# badge.net
KiCad netlist of a schematic drawn in EAGLE
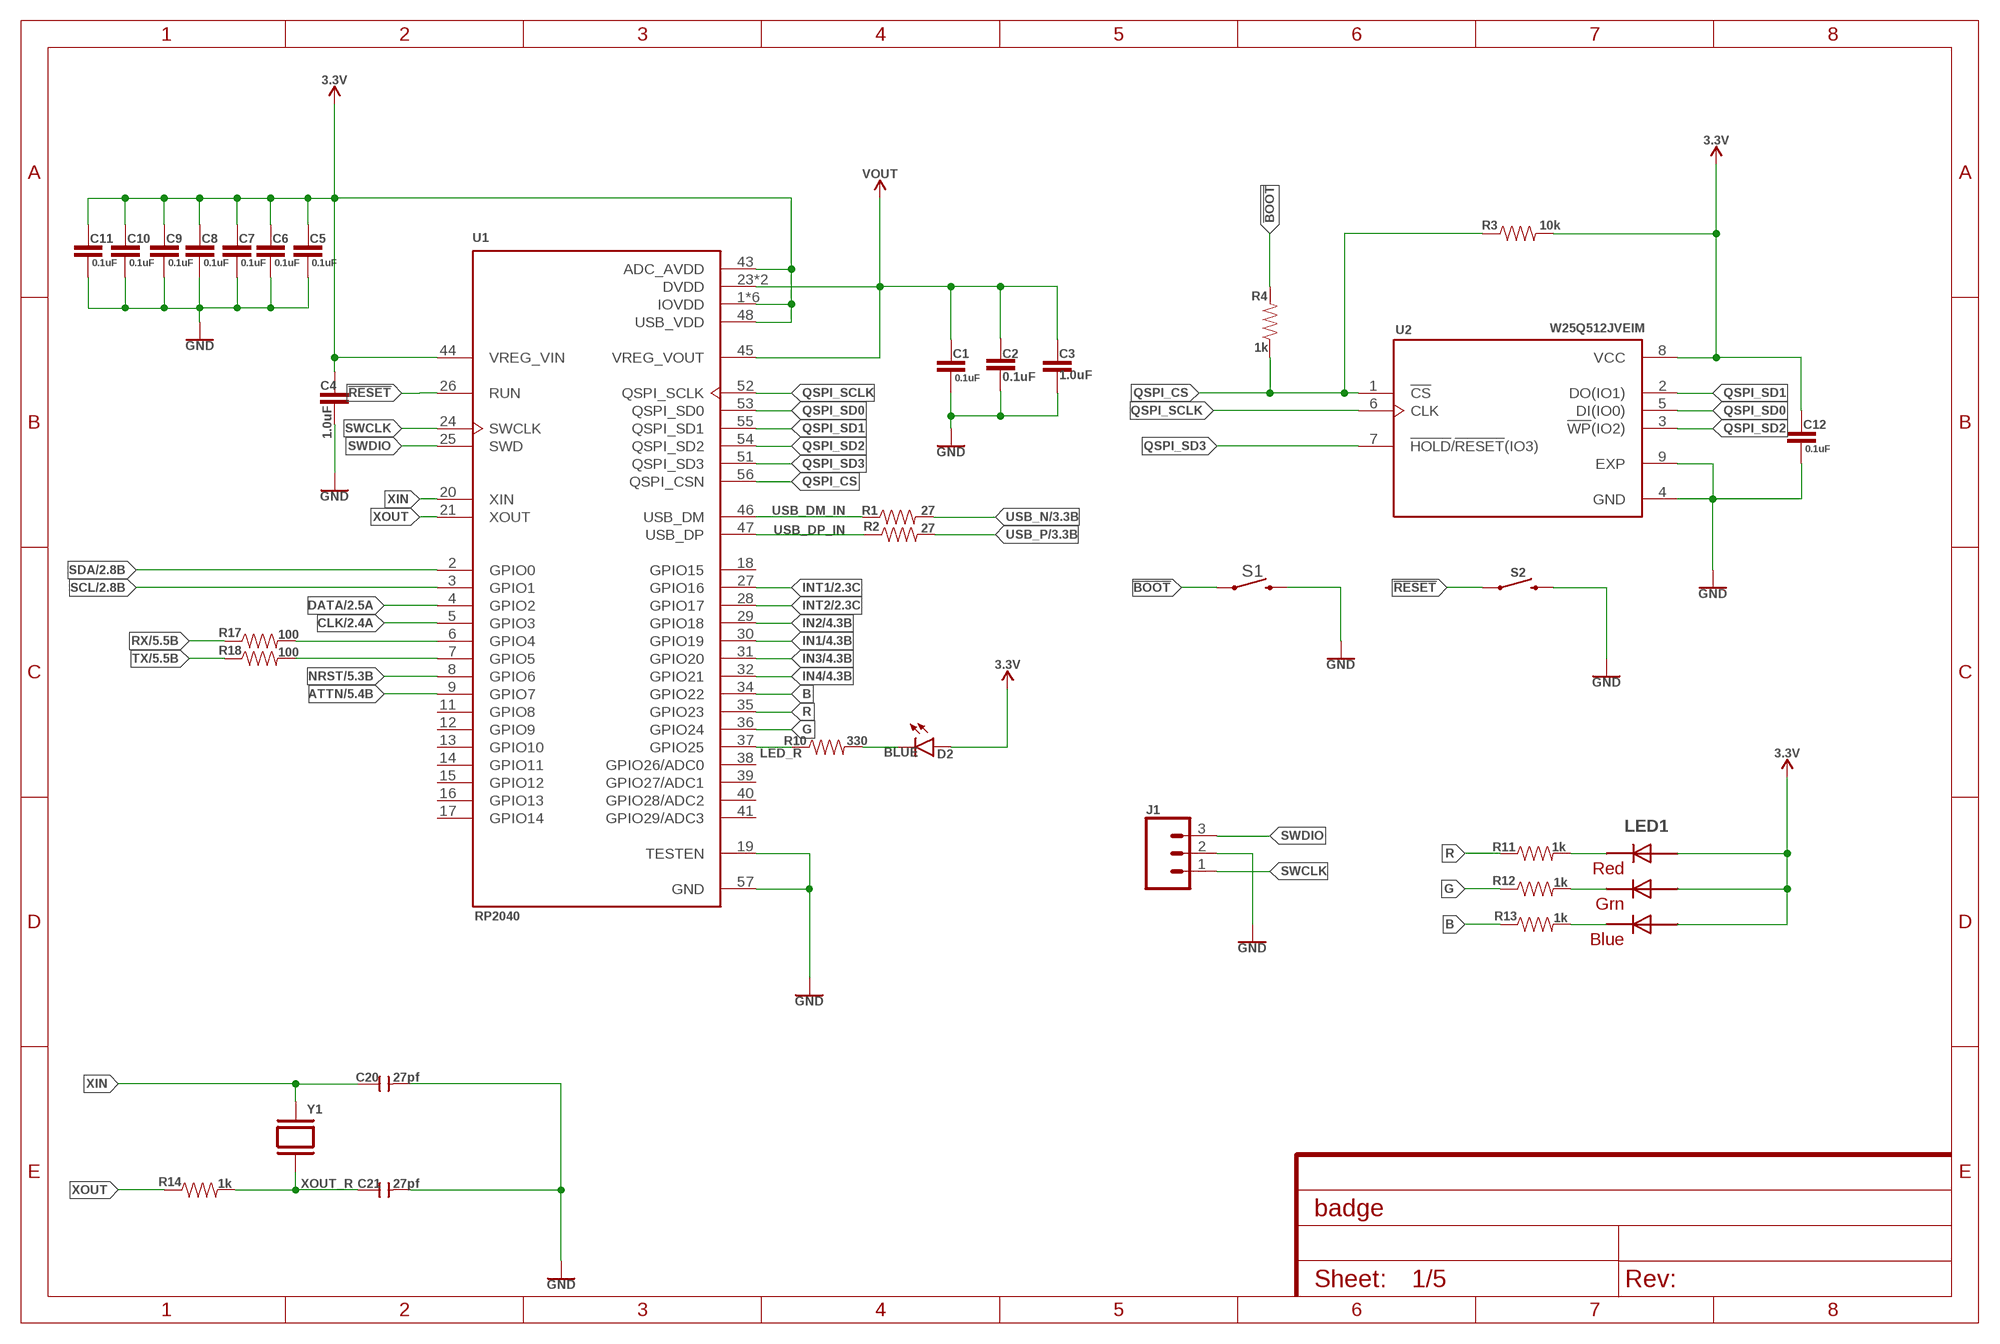
[diagram p0: schematic, sheet 1]
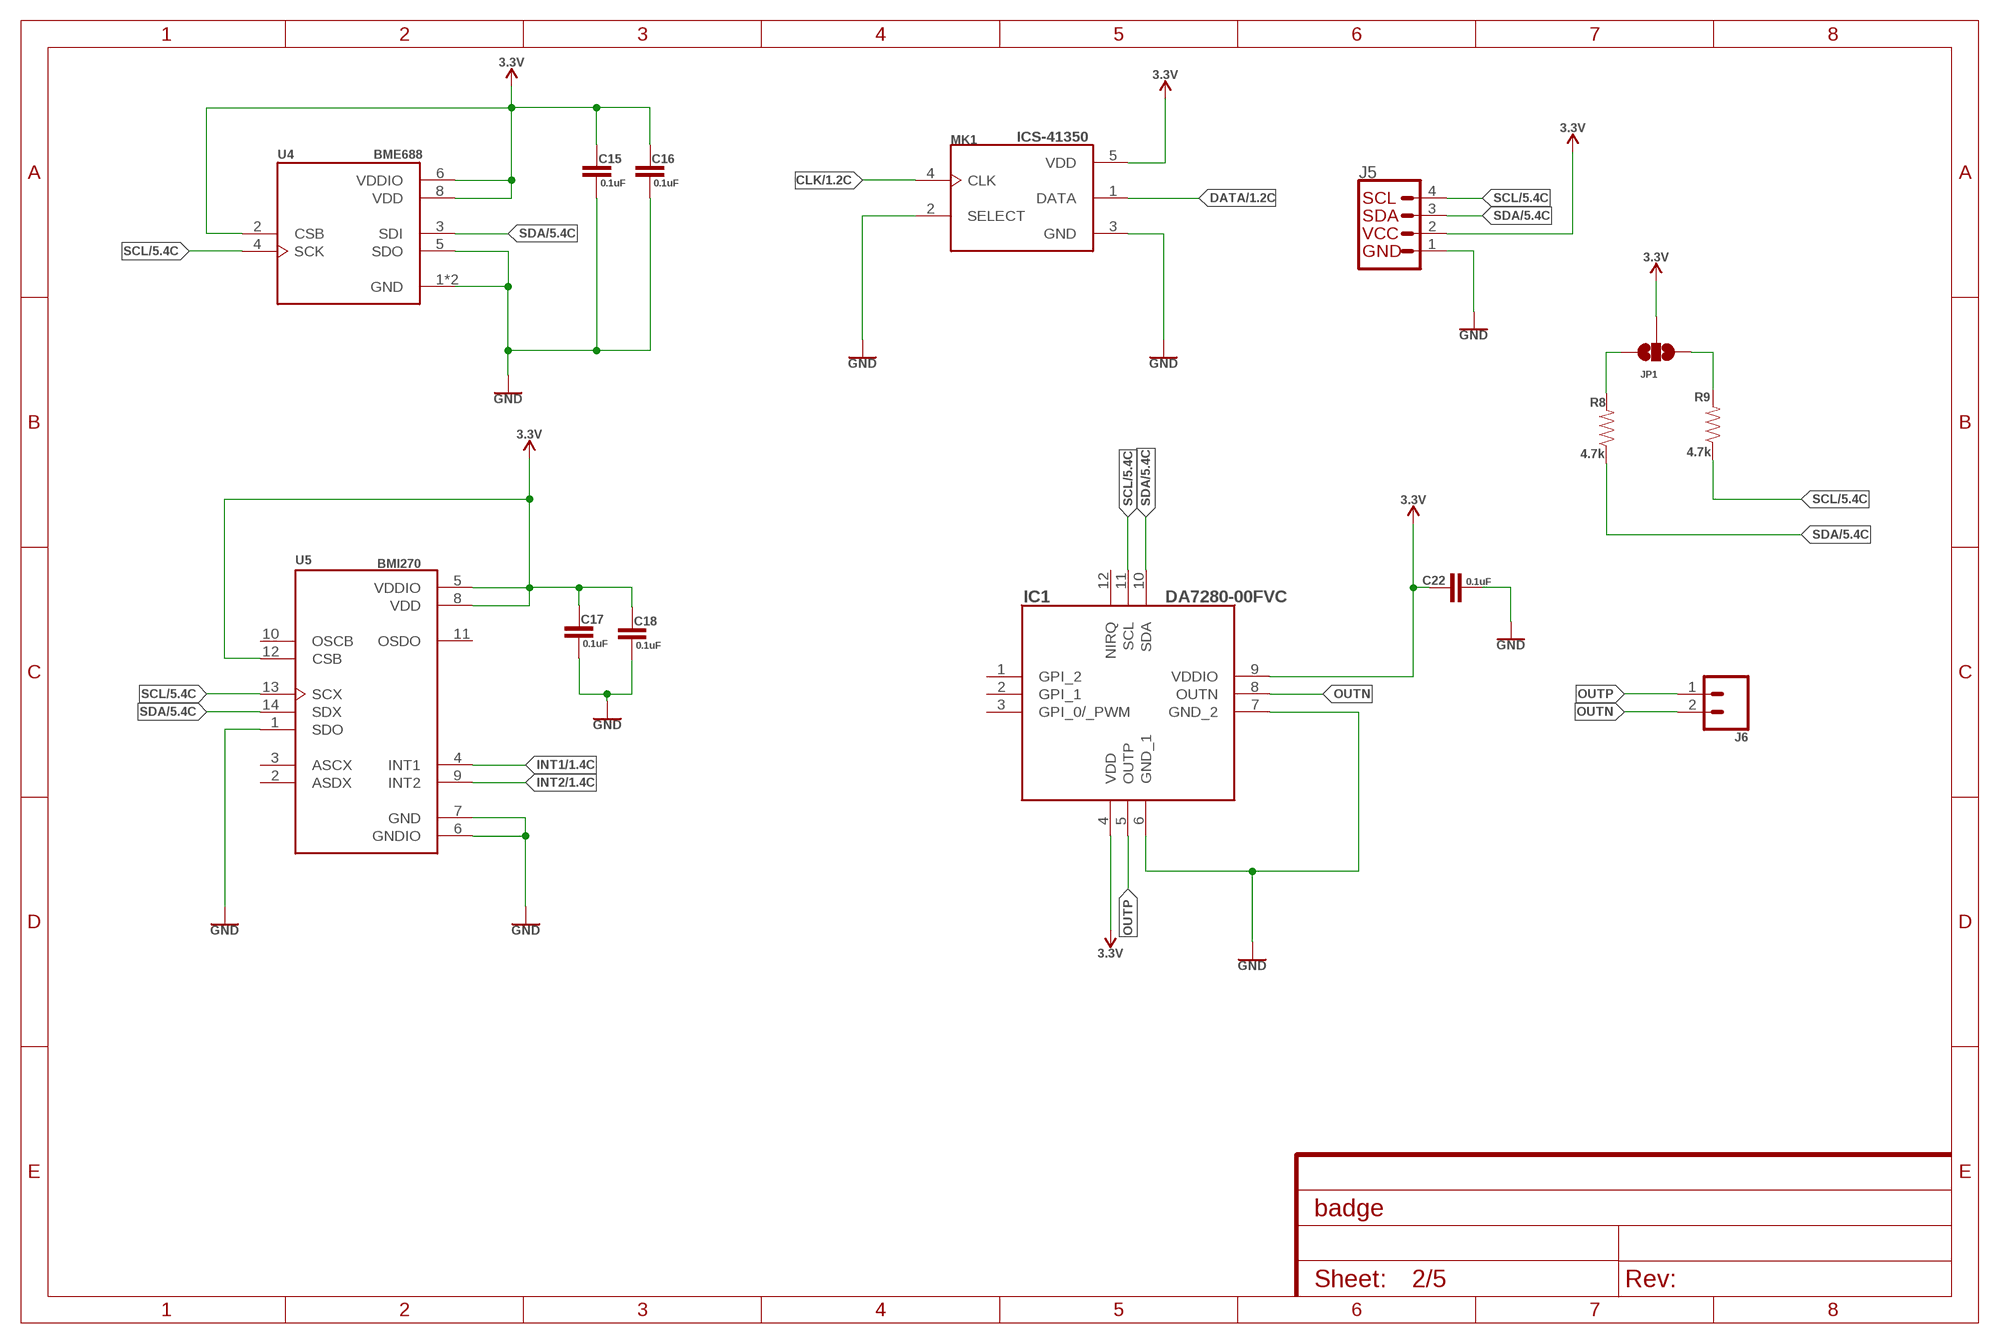
[diagram p1: schematic, sheet 2]
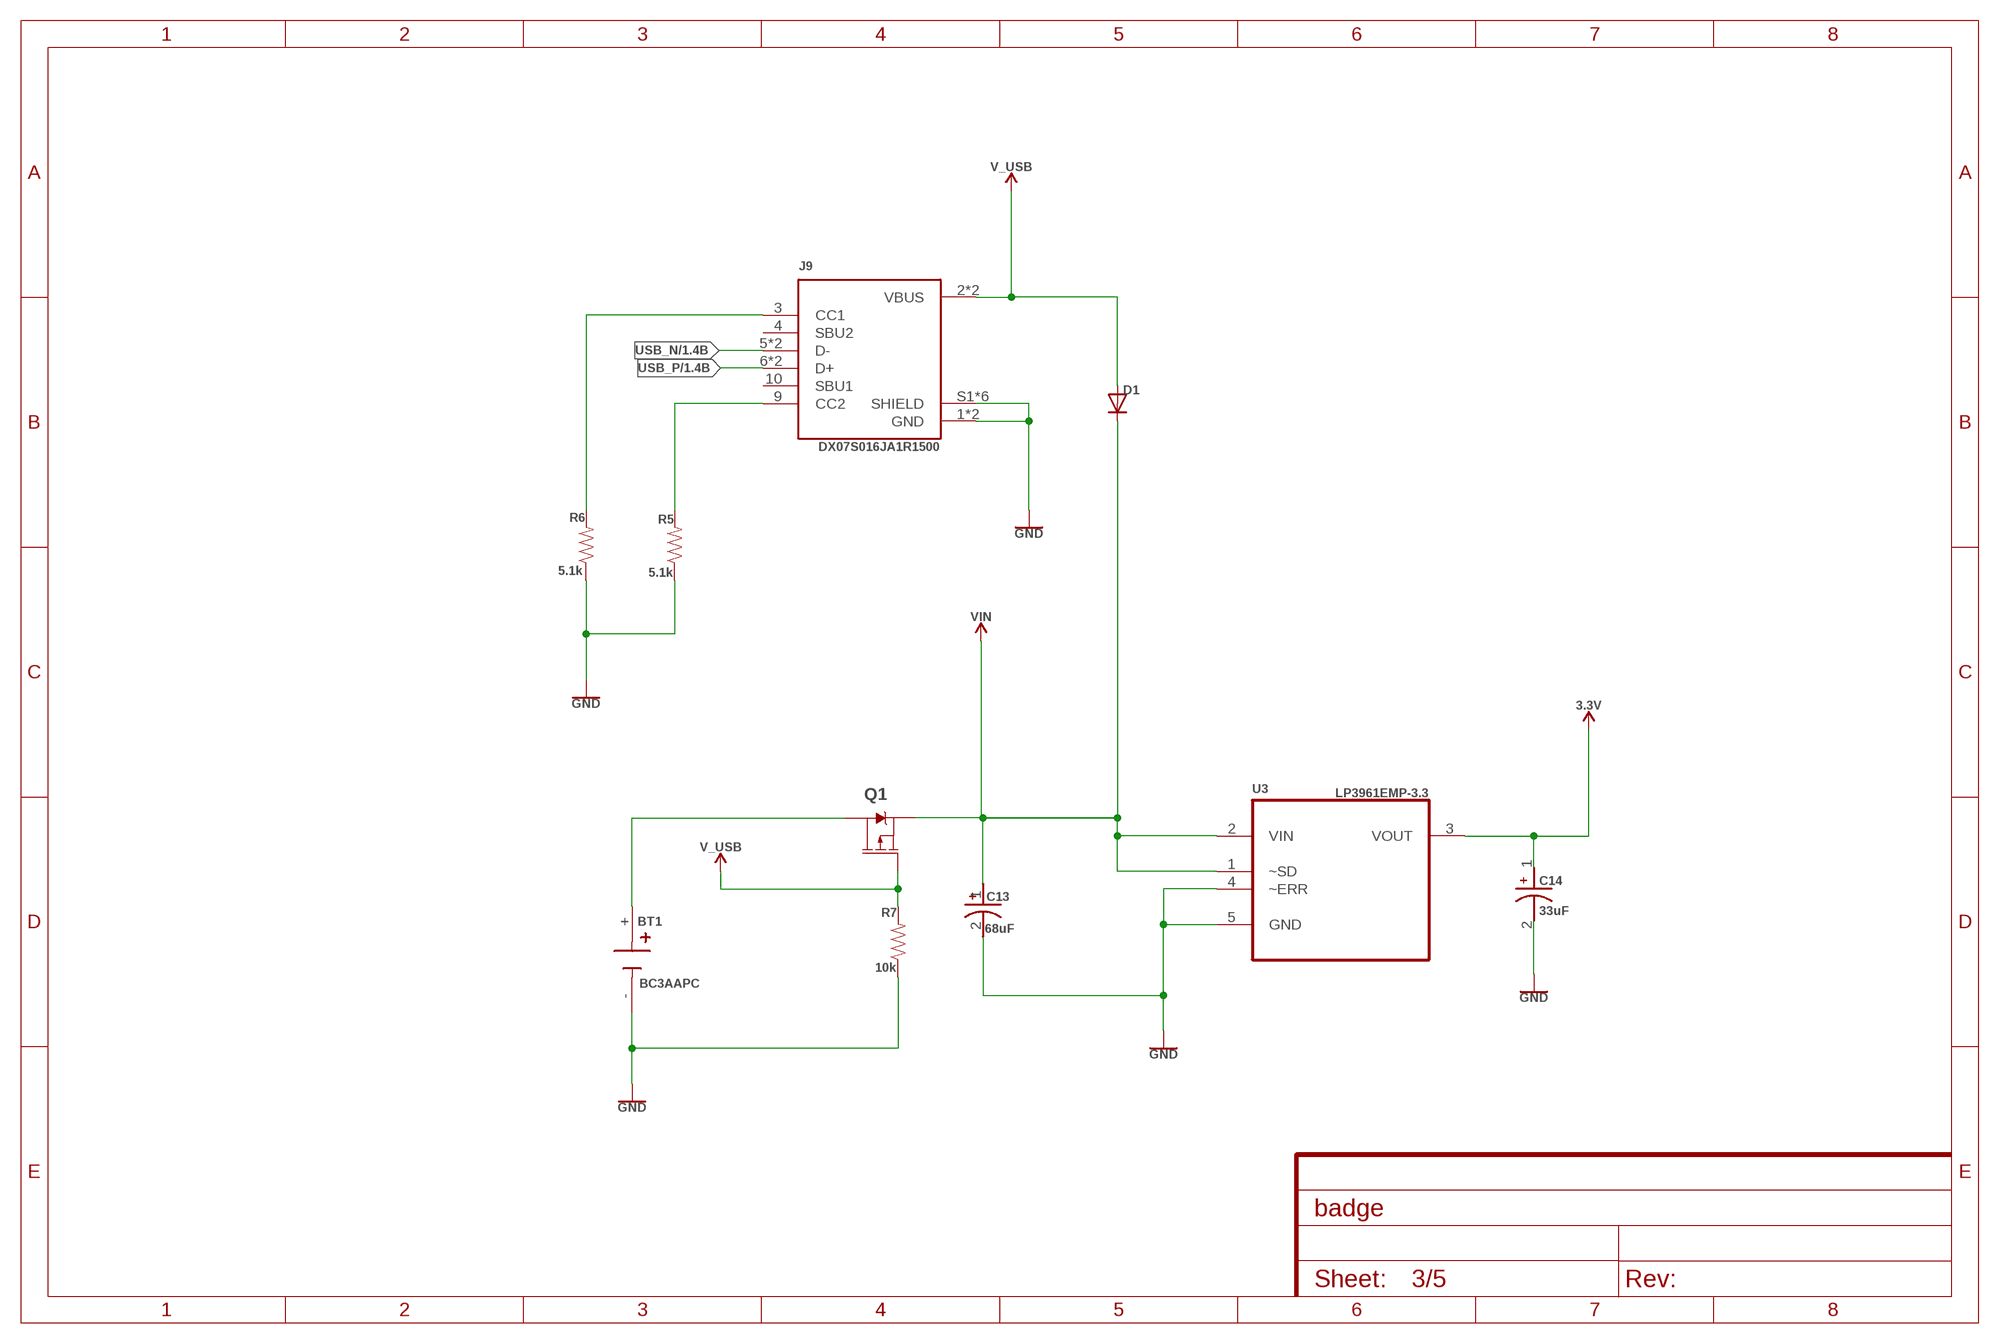
[diagram p2: schematic, sheet 3]
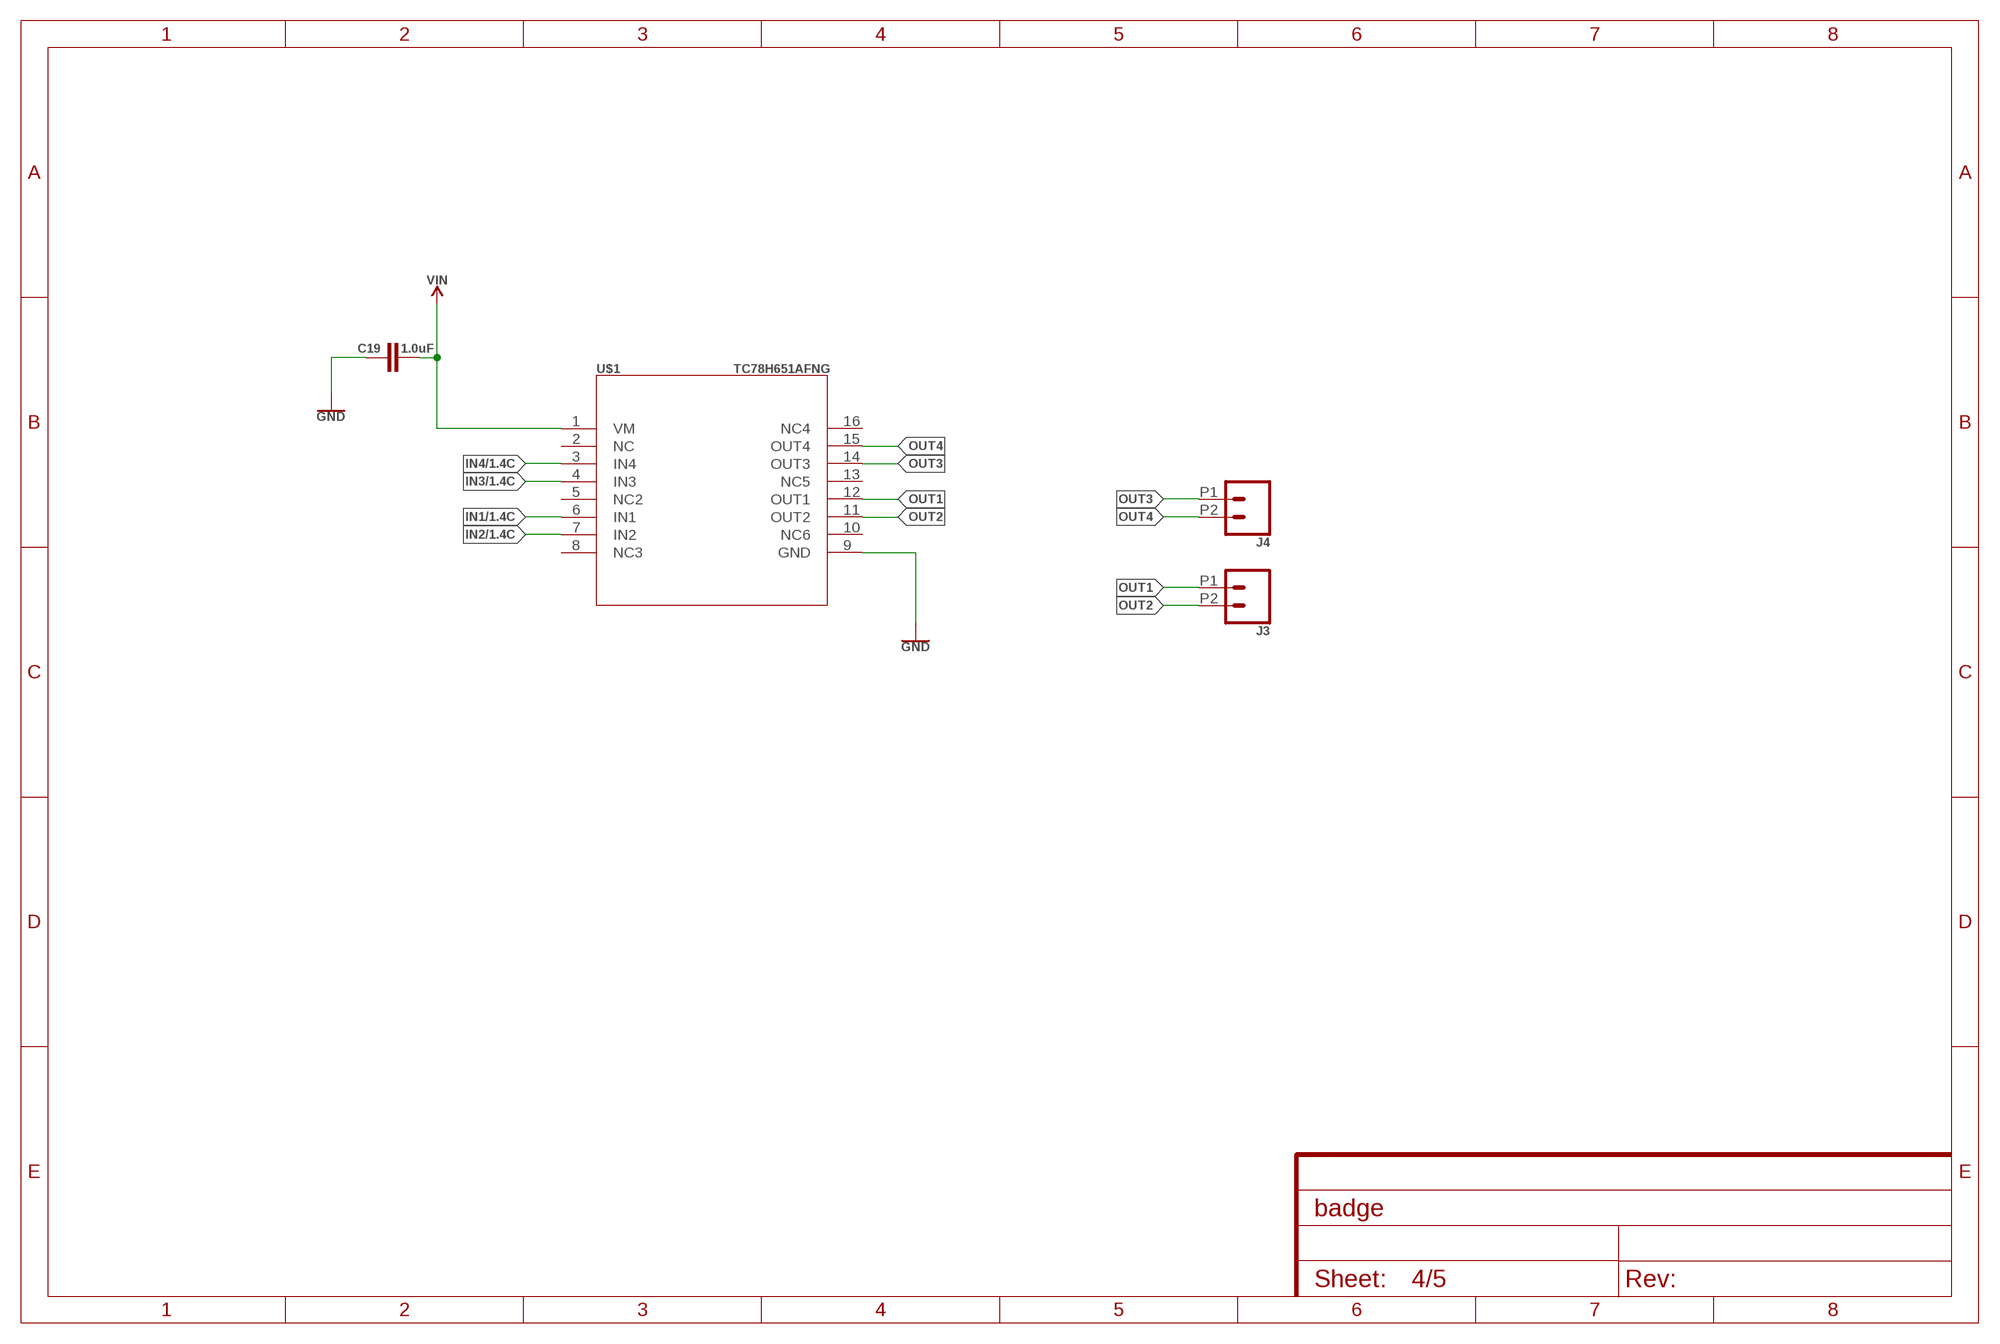
[diagram p3: schematic, sheet 4]
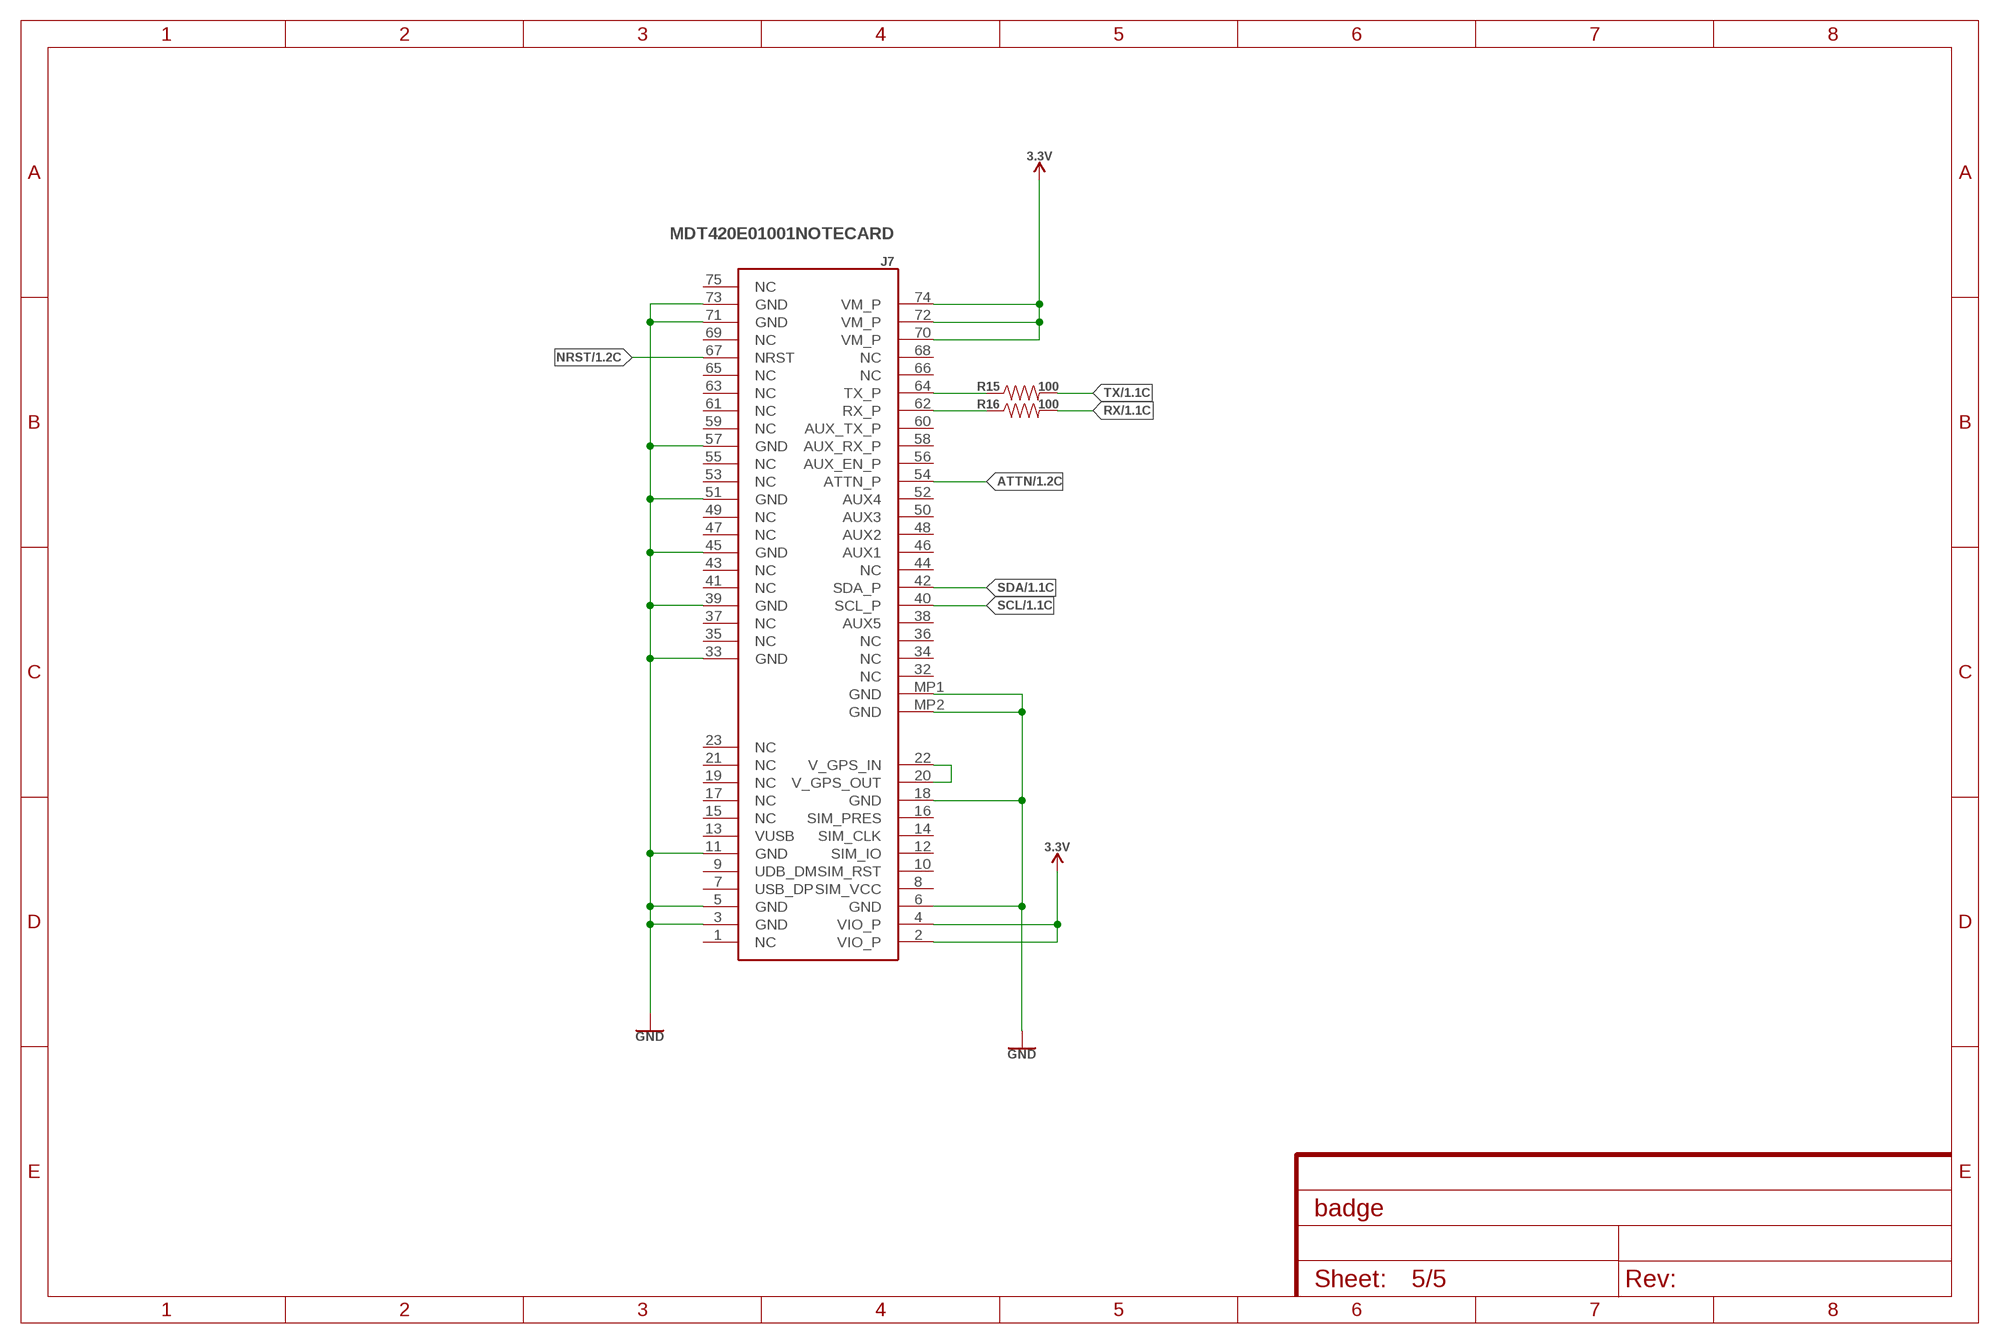
[diagram p4: schematic, sheet 5]

(export (version "E")
  (design (tool "Eeschema 10.0.6"))
  (components
    (comp (ref "C1")
      (value "0.1uF")
      (footprint "eagle-import:0603")
      (libsource (lib "eagle-import") (part "0.1UF-0603-25V-(+80/-20%)"))
    )
    (comp (ref "C2")
      (value "0.1uF")
      (footprint "eagle-import:0603")
      (libsource (lib "eagle-import") (part "0.1UF-0603-25V-(+80/-20%)"))
    )
    (comp (ref "C3")
      (value "1.0uF")
      (footprint "eagle-import:0603")
      (libsource (lib "eagle-import") (part "1.0UF-0603-16V-10%"))
    )
    (comp (ref "C4")
      (value "1.0uF")
      (footprint "eagle-import:0603")
      (libsource (lib "eagle-import") (part "1.0UF-0603-16V-10%"))
    )
    (comp (ref "C5")
      (value "0.1uF")
      (footprint "eagle-import:0603")
      (libsource (lib "eagle-import") (part "0.1UF-0603-25V-(+80/-20%)"))
    )
    (comp (ref "C6")
      (value "0.1uF")
      (footprint "eagle-import:0603")
      (libsource (lib "eagle-import") (part "0.1UF-0603-25V-(+80/-20%)"))
    )
    (comp (ref "C7")
      (value "0.1uF")
      (footprint "eagle-import:0603")
      (libsource (lib "eagle-import") (part "0.1UF-0603-25V-(+80/-20%)"))
    )
    (comp (ref "C8")
      (value "0.1uF")
      (footprint "eagle-import:0603")
      (libsource (lib "eagle-import") (part "0.1UF-0603-25V-(+80/-20%)"))
    )
    (comp (ref "C9")
      (value "0.1uF")
      (footprint "eagle-import:0603")
      (libsource (lib "eagle-import") (part "0.1UF-0603-25V-(+80/-20%)"))
    )
    (comp (ref "C10")
      (value "0.1uF")
      (footprint "eagle-import:0603")
      (libsource (lib "eagle-import") (part "0.1UF-0603-25V-(+80/-20%)"))
    )
    (comp (ref "C11")
      (value "0.1uF")
      (footprint "eagle-import:0603")
      (libsource (lib "eagle-import") (part "0.1UF-0603-25V-(+80/-20%)"))
    )
    (comp (ref "C12")
      (value "0.1uF")
      (footprint "eagle-import:0603")
      (libsource (lib "eagle-import") (part "0.1UF-0603-25V-(+80/-20%)"))
    )
    (comp (ref "C20")
      (value "27pf")
      (footprint "eagle-import:C0603")
      (fields (field (name "MPN") "CC0603JRNPO9BN270"))
      (libsource (lib "eagle-import") (part "CERAMIC-27PF-50V-5%-NPO(0603)"))
    )
    (comp (ref "C21")
      (value "27pf")
      (footprint "eagle-import:C0603")
      (fields (field (name "MPN") "CC0603JRNPO9BN270"))
      (libsource (lib "eagle-import") (part "CERAMIC-27PF-50V-5%-NPO(0603)"))
    )
    (comp (ref "D2")
      (value "BLUE")
      (footprint "eagle-import:LED-0603")
      (libsource (lib "eagle-import") (part "LED-BLUE0603"))
    )
    (comp (ref "J1")
      (value "CONN_03LONGPADS")
      (footprint "eagle-import:1X03_LONGPADS")
      (libsource (lib "eagle-import") (part "CONN_03LONGPADS"))
    )
    (comp (ref "LED1")
      (value "RGBLED5050")
      (footprint "eagle-import:RGBLED5050")
      (libsource (lib "eagle-import") (part "RGBLED5050"))
    )
    (comp (ref "R1")
      (value "27")
      (footprint "eagle-import:0603")
      (libsource (lib "eagle-import") (part "27OHM-0603-1/10W-1%"))
    )
    (comp (ref "R2")
      (value "27")
      (footprint "eagle-import:0603")
      (libsource (lib "eagle-import") (part "27OHM-0603-1/10W-1%"))
    )
    (comp (ref "R3")
      (value "10k")
      (footprint "eagle-import:0603")
      (libsource (lib "eagle-import") (part "10KOHM-0603-1/10W-1%"))
    )
    (comp (ref "R4")
      (value "1k")
      (footprint "eagle-import:0603")
      (libsource (lib "eagle-import") (part "1KOHM-0603-1/10W-1%"))
    )
    (comp (ref "R10")
      (value "330")
      (footprint "eagle-import:0603")
      (libsource (lib "eagle-import") (part "330OHM-0603-1/10W-1%"))
    )
    (comp (ref "R11")
      (value "1k")
      (footprint "eagle-import:0603")
      (libsource (lib "eagle-import") (part "1KOHM-0603-1/10W-1%"))
    )
    (comp (ref "R12")
      (value "1k")
      (footprint "eagle-import:0603")
      (libsource (lib "eagle-import") (part "1KOHM-0603-1/10W-1%"))
    )
    (comp (ref "R13")
      (value "1k")
      (footprint "eagle-import:0603")
      (libsource (lib "eagle-import") (part "1KOHM-0603-1/10W-1%"))
    )
    (comp (ref "R14")
      (value "1k")
      (footprint "eagle-import:0603")
      (libsource (lib "eagle-import") (part "1KOHM-0603-1/10W-1%"))
    )
    (comp (ref "R17")
      (value "100")
      (footprint "eagle-import:0603")
      (libsource (lib "eagle-import") (part "100OHM-0603-1/4W-5%"))
    )
    (comp (ref "R18")
      (value "100")
      (footprint "eagle-import:0603")
      (libsource (lib "eagle-import") (part "100OHM-0603-1/4W-5%"))
    )
    (comp (ref "S1")
      (value "MOMENTARY-SWITCH-SPST-SMD-6.0X3.5MM")
      (footprint "eagle-import:TACTILE_SWITCH_SMD_6.0X3.5MM")
      (libsource (lib "eagle-import") (part "MOMENTARY-SWITCH-SPST-SMD-6.0X3.5MM"))
    )
    (comp (ref "S2")
      (value "MOMENTARY-SWITCH-SPST-SMD-6.0X3.5MM")
      (footprint "eagle-import:TACTILE_SWITCH_SMD_6.0X3.5MM")
      (libsource (lib "eagle-import") (part "MOMENTARY-SWITCH-SPST-SMD-6.0X3.5MM"))
    )
    (comp (ref "U1")
      (value "RP2040")
      (footprint "eagle-import:QFN40P700X700X90-57N")
      (fields (field (name "MF") "Raspberry Pi"))
      (libsource (lib "eagle-import") (part "RP2040"))
    )
    (comp (ref "U2")
      (value "W25Q512JVEIM")
      (footprint "eagle-import:SON127P600X800X80-9N")
      (fields (field (name "MF") "Winbond Electronics"))
      (libsource (lib "eagle-import") (part "W25Q512JVEIM"))
    )
    (comp (ref "Y1")
      (value "ABLS-12.000MHZ-B4-T")
      (footprint "eagle-import:XTAL_ABLS-12.000MHZ-B4-T")
      (fields (field (name "MF") "Abracon LLC"))
      (libsource (lib "eagle-import") (part "ABLS-12.000MHZ-B4-T"))
    )
    (comp (ref "C15")
      (value "0.1uF")
      (footprint "eagle-import:0603")
      (libsource (lib "eagle-import") (part "0.1UF-0603-25V-(+80/-20%)"))
    )
    (comp (ref "C16")
      (value "0.1uF")
      (footprint "eagle-import:0603")
      (libsource (lib "eagle-import") (part "0.1UF-0603-25V-(+80/-20%)"))
    )
    (comp (ref "C17")
      (value "0.1uF")
      (footprint "eagle-import:0603")
      (libsource (lib "eagle-import") (part "0.1UF-0603-25V-(+80/-20%)"))
    )
    (comp (ref "C18")
      (value "0.1uF")
      (footprint "eagle-import:0603")
      (libsource (lib "eagle-import") (part "0.1UF-0603-25V-(+80/-20%)"))
    )
    (comp (ref "C22")
      (value "0.1uF")
      (footprint "eagle-import:0603")
      (libsource (lib "eagle-import") (part "0.1UF-0603-25V-(+80/-20%)"))
    )
    (comp (ref "IC1")
      (value "DA7280-00FVC")
      (footprint "eagle-import:QFN65P300X300X84-12N")
      (libsource (lib "eagle-import") (part "DA7280-00FVC"))
    )
    (comp (ref "J5")
      (value "QWIIC_CONNECTORJS-1MM")
      (footprint "eagle-import:1X04_1MM_RA")
      (libsource (lib "eagle-import") (part "QWIIC_CONNECTORJS-1MM"))
    )
    (comp (ref "J6")
      (value "CONN_02")
      (footprint "eagle-import:1X02")
      (libsource (lib "eagle-import") (part "SparkFun-Connectors_513_CONN_02"))
    )
    (comp (ref "JP1")
      (value "JUMPER-SMT_3_NO_SILK")
      (footprint "eagle-import:SMT-JUMPER_3_NO_SILK")
      (libsource (lib "eagle-import") (part "JUMPER-SMT_3_NO_SILK"))
    )
    (comp (ref "MK1")
      (value "ICS-41350")
      (footprint "eagle-import:MIC_ICS-41350")
      (fields (field (name "MF") "TDK InvenSense"))
      (libsource (lib "eagle-import") (part "ICS-41350"))
    )
    (comp (ref "R8")
      (value "4.7k")
      (footprint "eagle-import:0603")
      (libsource (lib "eagle-import") (part "4.7KOHM-0603-1/10W-1%"))
    )
    (comp (ref "R9")
      (value "4.7k")
      (footprint "eagle-import:0603")
      (libsource (lib "eagle-import") (part "4.7KOHM-0603-1/10W-1%"))
    )
    (comp (ref "U4")
      (value "BME688")
      (footprint "eagle-import:IC_BME688")
      (fields (field (name "MF") "Bosch Sensortec"))
      (libsource (lib "eagle-import") (part "BME688"))
    )
    (comp (ref "U5")
      (value "BMI270")
      (footprint "eagle-import:XDCR_BMI270")
      (fields (field (name "MF") "Bosch Sensortec"))
      (libsource (lib "eagle-import") (part "BMI270"))
    )
    (comp (ref "C19")
      (value "1.0uF")
      (footprint "eagle-import:0603")
      (libsource (lib "eagle-import") (part "1.0UF-0603-16V-10%"))
    )
    (comp (ref "J3")
      (value "CONN_022.54MM_SCREWTERM")
      (footprint "eagle-import:1X02_2.54_SCREWTERM")
      (libsource (lib "eagle-import") (part "CONN_022.54MM_SCREWTERM"))
    )
    (comp (ref "J4")
      (value "CONN_022.54MM_SCREWTERM")
      (footprint "eagle-import:1X02_2.54_SCREWTERM")
      (libsource (lib "eagle-import") (part "CONN_022.54MM_SCREWTERM"))
    )
    (comp (ref "U$1")
      (value "TC78H651AFNG")
      (footprint "eagle-import:P-TSSOP16-0505-0.65-001")
      (fields (field (name "MF") "Toshiba"))
      (libsource (lib "eagle-import") (part "TC78H651AFNG"))
    )
    (comp (ref "BT1")
      (value "BC3AAPC")
      (footprint "eagle-import:BAT_BC3AAPC")
      (fields (field (name "MF") "MPD"))
      (libsource (lib "eagle-import") (part "BC3AAPC"))
    )
    (comp (ref "C13")
      (value "68uF")
      (footprint "eagle-import:CAPMP3216X180N")
      (fields (field (name "MF") "KEMET") (field (name "MP") "T491A686M006AT"))
      (libsource (lib "eagle-import") (part "T491A686M006AT"))
    )
    (comp (ref "C14")
      (value "33uF")
      (footprint "eagle-import:CAPMP3216X180N")
      (fields (field (name "MF") "AVX") (field (name "MP") "TAJA336K006RNJ"))
      (libsource (lib "eagle-import") (part "TAJA336K006RNJ"))
    )
    (comp (ref "D1")
      (value "DIODESOD-123")
      (footprint "eagle-import:SOD-123")
      (libsource (lib "eagle-import") (part "DIODESOD-123"))
    )
    (comp (ref "J9")
      (value "DX07S016JA1R1500")
      (footprint "eagle-import:JAE_DX07S016JA1R1500")
      (fields (field (name "MF") "JAE Electronics"))
      (libsource (lib "eagle-import") (part "DX07S016JA1R1500"))
    )
    (comp (ref "Q1")
      (value "2.5A/30V/105mΩ")
      (footprint "eagle-import:SOT23-3")
      (libsource (lib "eagle-import") (part "MOSFET_PCH-DMG2307L"))
    )
    (comp (ref "R5")
      (value "5.1k")
      (footprint "eagle-import:0603")
      (libsource (lib "eagle-import") (part "5.6KOHM-0603-1/10W-1%"))
    )
    (comp (ref "R6")
      (value "5.1k")
      (footprint "eagle-import:0603")
      (libsource (lib "eagle-import") (part "5.6KOHM-0603-1/10W-1%"))
    )
    (comp (ref "R7")
      (value "10k")
      (footprint "eagle-import:0603")
      (libsource (lib "eagle-import") (part "10KOHM-0603-1/10W-1%"))
    )
    (comp (ref "U3")
      (value "LP3961EMP-3.3")
      (footprint "eagle-import:SOT150P696X180-5N")
      (fields
        (field (name "DIGI-KEY_PART_NUMBER") "LP3961EMP-3.3/NOPBTR-ND")
        (field (name "MF") "Texas Instruments")
        (field (name "MP") "LP3961EMP-3.3/NOPB")
      )
      (libsource (lib "eagle-import") (part "LP3961EMP-3.3"))
    )
    (comp (ref "J7")
      (value "MDT420E01001NOTECARD")
      (footprint "eagle-import:NOTECARD")
      (libsource (lib "eagle-import") (part "MDT420E01001NOTECARD"))
    )
    (comp (ref "R15")
      (value "100")
      (footprint "eagle-import:0603")
      (libsource (lib "eagle-import") (part "100OHM-0603-1/4W-5%"))
    )
    (comp (ref "R16")
      (value "100")
      (footprint "eagle-import:0603")
      (libsource (lib "eagle-import") (part "100OHM-0603-1/4W-5%"))
    )
  )
  (nets
    (net (code "1") (name "3.3V") (class "Default")
      (node (ref "C10") (pin "1") (pinfunction "1_1") (pintype "passive"))
      (node (ref "C11") (pin "1") (pinfunction "1_1") (pintype "passive"))
      (node (ref "C12") (pin "1") (pinfunction "1_1") (pintype "passive"))
      (node (ref "C14") (pin "1") (pinfunction "1_1") (pintype "passive"))
      (node (ref "C15") (pin "1") (pinfunction "1_1") (pintype "passive"))
      (node (ref "C16") (pin "1") (pinfunction "1_1") (pintype "passive"))
      (node (ref "C17") (pin "1") (pinfunction "1_1") (pintype "passive"))
      (node (ref "C18") (pin "1") (pinfunction "1_1") (pintype "passive"))
      (node (ref "C22") (pin "1") (pinfunction "1_1") (pintype "passive"))
      (node (ref "C4") (pin "1") (pinfunction "1_1") (pintype "passive"))
      (node (ref "C5") (pin "1") (pinfunction "1_1") (pintype "passive"))
      (node (ref "C6") (pin "1") (pinfunction "1_1") (pintype "passive"))
      (node (ref "C7") (pin "1") (pinfunction "1_1") (pintype "passive"))
      (node (ref "C8") (pin "1") (pinfunction "1_1") (pintype "passive"))
      (node (ref "C9") (pin "1") (pinfunction "1_1") (pintype "passive"))
      (node (ref "D2") (pin "A") (pinfunction "A_A") (pintype "passive"))
      (node (ref "IC1") (pin "4") (pinfunction "VDD_4") (pintype "bidirectional"))
      (node (ref "IC1") (pin "9") (pinfunction "VDDIO_9") (pintype "bidirectional"))
      (node (ref "J5") (pin "2") (pinfunction "VCC_2") (pintype "power_in"))
      (node (ref "J7") (pin "2") (pinfunction "VIO_P_2") (pintype "bidirectional"))
      (node (ref "J7") (pin "4") (pinfunction "VIO_P_4") (pintype "bidirectional"))
      (node (ref "J7") (pin "70") (pinfunction "VM_P_70") (pintype "bidirectional"))
      (node (ref "J7") (pin "72") (pinfunction "VM_P_72") (pintype "bidirectional"))
      (node (ref "J7") (pin "74") (pinfunction "VM_P_74") (pintype "bidirectional"))
      (node (ref "JP1") (pin "2") (pinfunction "2_2") (pintype "passive"))
      (node (ref "LED1") (pin "1") (pinfunction "GREEN_A_1") (pintype "bidirectional"))
      (node (ref "LED1") (pin "2") (pinfunction "RED_A_2") (pintype "bidirectional"))
      (node (ref "LED1") (pin "3") (pinfunction "BLUE_A_3") (pintype "bidirectional"))
      (node (ref "MK1") (pin "5") (pinfunction "VDD_5") (pintype "power_in"))
      (node (ref "R3") (pin "2") (pinfunction "2_2") (pintype "passive"))
      (node (ref "U1") (pin "1") (pinfunction "IOVDD_1") (pintype "power_in"))
      (node (ref "U1") (pin "10") (pinfunction "IOVDD_10") (pintype "power_in"))
      (node (ref "U1") (pin "22") (pinfunction "IOVDD_22") (pintype "power_in"))
      (node (ref "U1") (pin "33") (pinfunction "IOVDD_33") (pintype "power_in"))
      (node (ref "U1") (pin "42") (pinfunction "IOVDD_42") (pintype "power_in"))
      (node (ref "U1") (pin "43") (pinfunction "ADC_AVDD_43") (pintype "power_in"))
      (node (ref "U1") (pin "44") (pinfunction "VREG_VIN_44") (pintype "input"))
      (node (ref "U1") (pin "48") (pinfunction "USB_VDD_48") (pintype "power_in"))
      (node (ref "U1") (pin "49") (pinfunction "IOVDD_49") (pintype "power_in"))
      (node (ref "U2") (pin "8") (pinfunction "VCC_8") (pintype "power_in"))
      (node (ref "U3") (pin "3") (pinfunction "VOUT_3") (pintype "output"))
      (node (ref "U4") (pin "2") (pinfunction "CSB_2") (pintype "input"))
      (node (ref "U4") (pin "6") (pinfunction "VDDIO_6") (pintype "power_in"))
      (node (ref "U4") (pin "8") (pinfunction "VDD_8") (pintype "power_in"))
      (node (ref "U5") (pin "12") (pinfunction "CSB_12") (pintype "input"))
      (node (ref "U5") (pin "5") (pinfunction "VDDIO_5") (pintype "power_in"))
      (node (ref "U5") (pin "8") (pinfunction "VDD_8") (pintype "power_in"))
    )
    (net (code "2") (name "ATTN") (class "Default")
      (node (ref "J7") (pin "54") (pinfunction "ATTN_P_54") (pintype "bidirectional"))
      (node (ref "U1") (pin "9") (pinfunction "GPIO7_9") (pintype "bidirectional"))
    )
    (net (code "3") (name "B") (class "Default")
      (node (ref "R13") (pin "1") (pinfunction "1_1") (pintype "passive"))
      (node (ref "U1") (pin "34") (pinfunction "GPIO22_34") (pintype "bidirectional"))
    )
    (net (code "4") (name "CLK") (class "Default")
      (node (ref "MK1") (pin "4") (pinfunction "CLK_4") (pintype "input"))
      (node (ref "U1") (pin "5") (pinfunction "GPIO3_5") (pintype "bidirectional"))
    )
    (net (code "5") (name "DATA") (class "Default")
      (node (ref "MK1") (pin "1") (pinfunction "DATA_1") (pintype "output"))
      (node (ref "U1") (pin "4") (pinfunction "GPIO2_4") (pintype "bidirectional"))
    )
    (net (code "6") (name "G") (class "Default")
      (node (ref "R12") (pin "1") (pinfunction "1_1") (pintype "passive"))
      (node (ref "U1") (pin "36") (pinfunction "GPIO24_36") (pintype "bidirectional"))
    )
    (net (code "7") (name "GND") (class "Default")
      (node (ref "BT1") (pin "-") (pinfunction "-_-") (pintype "passive"))
      (node (ref "C1") (pin "2") (pinfunction "2_2") (pintype "passive"))
      (node (ref "C10") (pin "2") (pinfunction "2_2") (pintype "passive"))
      (node (ref "C11") (pin "2") (pinfunction "2_2") (pintype "passive"))
      (node (ref "C12") (pin "2") (pinfunction "2_2") (pintype "passive"))
      (node (ref "C13") (pin "2") (pinfunction "2_2") (pintype "passive"))
      (node (ref "C14") (pin "2") (pinfunction "2_2") (pintype "passive"))
      (node (ref "C15") (pin "2") (pinfunction "2_2") (pintype "passive"))
      (node (ref "C16") (pin "2") (pinfunction "2_2") (pintype "passive"))
      (node (ref "C17") (pin "2") (pinfunction "2_2") (pintype "passive"))
      (node (ref "C18") (pin "2") (pinfunction "2_2") (pintype "passive"))
      (node (ref "C19") (pin "1") (pinfunction "1_1") (pintype "passive"))
      (node (ref "C2") (pin "2") (pinfunction "2_2") (pintype "passive"))
      (node (ref "C20") (pin "2") (pinfunction "2_2") (pintype "passive"))
      (node (ref "C21") (pin "2") (pinfunction "2_2") (pintype "passive"))
      (node (ref "C22") (pin "2") (pinfunction "2_2") (pintype "passive"))
      (node (ref "C3") (pin "2") (pinfunction "2_2") (pintype "passive"))
      (node (ref "C4") (pin "2") (pinfunction "2_2") (pintype "passive"))
      (node (ref "C5") (pin "2") (pinfunction "2_2") (pintype "passive"))
      (node (ref "C6") (pin "2") (pinfunction "2_2") (pintype "passive"))
      (node (ref "C7") (pin "2") (pinfunction "2_2") (pintype "passive"))
      (node (ref "C8") (pin "2") (pinfunction "2_2") (pintype "passive"))
      (node (ref "C9") (pin "2") (pinfunction "2_2") (pintype "passive"))
      (node (ref "IC1") (pin "6") (pinfunction "GND_1_6") (pintype "bidirectional"))
      (node (ref "IC1") (pin "7") (pinfunction "GND_2_7") (pintype "bidirectional"))
      (node (ref "J1") (pin "2") (pinfunction "2_2") (pintype "passive"))
      (node (ref "J5") (pin "1") (pinfunction "GND_1") (pintype "power_in"))
      (node (ref "J7") (pin "11") (pinfunction "GND_11") (pintype "bidirectional"))
      (node (ref "J7") (pin "18") (pinfunction "GND_18") (pintype "bidirectional"))
      (node (ref "J7") (pin "3") (pinfunction "GND_3") (pintype "bidirectional"))
      (node (ref "J7") (pin "33") (pinfunction "GND_33") (pintype "bidirectional"))
      (node (ref "J7") (pin "39") (pinfunction "GND_39") (pintype "bidirectional"))
      (node (ref "J7") (pin "45") (pinfunction "GND_45") (pintype "bidirectional"))
      (node (ref "J7") (pin "5") (pinfunction "GND_5") (pintype "bidirectional"))
      (node (ref "J7") (pin "51") (pinfunction "GND_51") (pintype "bidirectional"))
      (node (ref "J7") (pin "57") (pinfunction "GND_57") (pintype "bidirectional"))
      (node (ref "J7") (pin "6") (pinfunction "GND_6") (pintype "bidirectional"))
      (node (ref "J7") (pin "71") (pinfunction "GND_71") (pintype "bidirectional"))
      (node (ref "J7") (pin "73") (pinfunction "GND_73") (pintype "bidirectional"))
      (node (ref "J7") (pin "MP1") (pinfunction "GND_MP1") (pintype "power_in"))
      (node (ref "J7") (pin "MP2") (pinfunction "GND_MP2") (pintype "bidirectional"))
      (node (ref "J9") (pin "1") (pinfunction "GND_1") (pintype "power_in"))
      (node (ref "J9") (pin "12") (pinfunction "GND_12") (pintype "power_in"))
      (node (ref "J9") (pin "S1") (pinfunction "SHIELD_S1") (pintype "passive"))
      (node (ref "J9") (pin "S2") (pinfunction "SHIELD_S2") (pintype "passive"))
      (node (ref "J9") (pin "S3") (pinfunction "SHIELD_S3") (pintype "passive"))
      (node (ref "J9") (pin "S4") (pinfunction "SHIELD_S4") (pintype "passive"))
      (node (ref "J9") (pin "S5") (pinfunction "SHIELD_S5") (pintype "passive"))
      (node (ref "J9") (pin "S6") (pinfunction "SHIELD_S6") (pintype "passive"))
      (node (ref "MK1") (pin "2") (pinfunction "SELECT_2") (pintype "input"))
      (node (ref "MK1") (pin "3") (pinfunction "GND_3") (pintype "power_in"))
      (node (ref "R5") (pin "1") (pinfunction "1_1") (pintype "passive"))
      (node (ref "R6") (pin "1") (pinfunction "1_1") (pintype "passive"))
      (node (ref "R7") (pin "1") (pinfunction "1_1") (pintype "passive"))
      (node (ref "S1") (pin "2") (pinfunction "2_2") (pintype "passive"))
      (node (ref "S2") (pin "2") (pinfunction "2_2") (pintype "passive"))
      (node (ref "U$1") (pin "9") (pinfunction "GND_9") (pintype "bidirectional"))
      (node (ref "U1") (pin "19") (pinfunction "TESTEN_19") (pintype "passive"))
      (node (ref "U1") (pin "57") (pinfunction "GND_57") (pintype "power_in"))
      (node (ref "U2") (pin "4") (pinfunction "GND_4") (pintype "power_in"))
      (node (ref "U2") (pin "9") (pinfunction "EXP_9") (pintype "passive"))
      (node (ref "U3") (pin "4") (pinfunction "~{ERR}_4") (pintype "passive"))
      (node (ref "U3") (pin "5") (pinfunction "GND_5") (pintype "passive"))
      (node (ref "U4") (pin "1") (pinfunction "GND_1") (pintype "power_in"))
      (node (ref "U4") (pin "5") (pinfunction "SDO_5") (pintype "bidirectional"))
      (node (ref "U4") (pin "7") (pinfunction "GND_7") (pintype "power_in"))
      (node (ref "U5") (pin "1") (pinfunction "SDO_1") (pintype "bidirectional"))
      (node (ref "U5") (pin "6") (pinfunction "GNDIO_6") (pintype "power_in"))
      (node (ref "U5") (pin "7") (pinfunction "GND_7") (pintype "power_in"))
    )
    (net (code "8") (name "IN1") (class "Default")
      (node (ref "U$1") (pin "6") (pinfunction "IN1_6") (pintype "bidirectional"))
      (node (ref "U1") (pin "30") (pinfunction "GPIO19_30") (pintype "bidirectional"))
    )
    (net (code "9") (name "IN2") (class "Default")
      (node (ref "U$1") (pin "7") (pinfunction "IN2_7") (pintype "bidirectional"))
      (node (ref "U1") (pin "29") (pinfunction "GPIO18_29") (pintype "bidirectional"))
    )
    (net (code "10") (name "IN3") (class "Default")
      (node (ref "U$1") (pin "4") (pinfunction "IN3_4") (pintype "bidirectional"))
      (node (ref "U1") (pin "31") (pinfunction "GPIO20_31") (pintype "bidirectional"))
    )
    (net (code "11") (name "IN4") (class "Default")
      (node (ref "U$1") (pin "3") (pinfunction "IN4_3") (pintype "bidirectional"))
      (node (ref "U1") (pin "32") (pinfunction "GPIO21_32") (pintype "bidirectional"))
    )
    (net (code "12") (name "INT1") (class "Default")
      (node (ref "U1") (pin "27") (pinfunction "GPIO16_27") (pintype "bidirectional"))
      (node (ref "U5") (pin "4") (pinfunction "INT1_4") (pintype "bidirectional"))
    )
    (net (code "13") (name "INT2") (class "Default")
      (node (ref "U1") (pin "28") (pinfunction "GPIO17_28") (pintype "bidirectional"))
      (node (ref "U5") (pin "9") (pinfunction "INT2_9") (pintype "bidirectional"))
    )
    (net (code "14") (name "LED_R") (class "Default")
      (node (ref "R10") (pin "1") (pinfunction "1_1") (pintype "passive"))
      (node (ref "U1") (pin "37") (pinfunction "GPIO25_37") (pintype "bidirectional"))
    )
    (net (code "15") (name "NRST") (class "Default")
      (node (ref "J7") (pin "67") (pinfunction "NRST_67") (pintype "bidirectional"))
      (node (ref "U1") (pin "8") (pinfunction "GPIO6_8") (pintype "bidirectional"))
    )
    (net (code "16") (name "Net-(D2-PadC)") (class "Default")
      (node (ref "D2") (pin "C") (pinfunction "C_C") (pintype "passive"))
      (node (ref "R10") (pin "2") (pinfunction "2_2") (pintype "passive"))
    )
    (net (code "17") (name "Net-(J7-RX_P)") (class "Default")
      (node (ref "J7") (pin "62") (pinfunction "RX_P_62") (pintype "bidirectional"))
      (node (ref "R16") (pin "1") (pinfunction "1_1") (pintype "passive"))
    )
    (net (code "18") (name "Net-(J7-TX_P)") (class "Default")
      (node (ref "J7") (pin "64") (pinfunction "TX_P_64") (pintype "bidirectional"))
      (node (ref "R15") (pin "1") (pinfunction "1_1") (pintype "passive"))
    )
    (net (code "19") (name "Net-(J7-V_GPS_IN)") (class "Default")
      (node (ref "J7") (pin "20") (pinfunction "V_GPS_OUT_20") (pintype "bidirectional"))
      (node (ref "J7") (pin "22") (pinfunction "V_GPS_IN_22") (pintype "bidirectional"))
    )
    (net (code "20") (name "Net-(J9-CC1)") (class "Default")
      (node (ref "J9") (pin "3") (pinfunction "CC1_3") (pintype "passive"))
      (node (ref "R6") (pin "2") (pinfunction "2_2") (pintype "passive"))
    )
    (net (code "21") (name "Net-(J9-CC2)") (class "Default")
      (node (ref "J9") (pin "9") (pinfunction "CC2_9") (pintype "passive"))
      (node (ref "R5") (pin "2") (pinfunction "2_2") (pintype "passive"))
    )
    (net (code "22") (name "Net-(JP1-Pad1)") (class "Default")
      (node (ref "JP1") (pin "1") (pinfunction "1_1") (pintype "passive"))
      (node (ref "R9") (pin "2") (pinfunction "2_2") (pintype "passive"))
    )
    (net (code "23") (name "Net-(JP1-Pad3)") (class "Default")
      (node (ref "JP1") (pin "3") (pinfunction "3_3") (pintype "passive"))
      (node (ref "R8") (pin "2") (pinfunction "2_2") (pintype "passive"))
    )
    (net (code "24") (name "Net-(LED1-BLUE_C)") (class "Default")
      (node (ref "LED1") (pin "4") (pinfunction "BLUE_C_4") (pintype "bidirectional"))
      (node (ref "R13") (pin "2") (pinfunction "2_2") (pintype "passive"))
    )
    (net (code "25") (name "Net-(LED1-GREEN_C)") (class "Default")
      (node (ref "LED1") (pin "6") (pinfunction "GREEN_C_6") (pintype "bidirectional"))
      (node (ref "R12") (pin "2") (pinfunction "2_2") (pintype "passive"))
    )
    (net (code "26") (name "Net-(LED1-RED_C)") (class "Default")
      (node (ref "LED1") (pin "5") (pinfunction "RED_C_5") (pintype "bidirectional"))
      (node (ref "R11") (pin "2") (pinfunction "2_2") (pintype "passive"))
    )
    (net (code "27") (name "Net-(Q1-D)") (class "Default")
      (node (ref "BT1") (pin "+") (pinfunction "+_+") (pintype "passive"))
      (node (ref "Q1") (pin "3") (pinfunction "D_3") (pintype "bidirectional"))
    )
    (net (code "28") (name "Net-(U1-GPIO4)") (class "Default")
      (node (ref "R17") (pin "2") (pinfunction "2_2") (pintype "passive"))
      (node (ref "U1") (pin "6") (pinfunction "GPIO4_6") (pintype "bidirectional"))
    )
    (net (code "29") (name "Net-(U1-GPIO5)") (class "Default")
      (node (ref "R18") (pin "2") (pinfunction "2_2") (pintype "passive"))
      (node (ref "U1") (pin "7") (pinfunction "GPIO5_7") (pintype "bidirectional"))
    )
    (net (code "30") (name "OUT1") (class "Default")
      (node (ref "J3") (pin "P1") (pinfunction "1_P1") (pintype "passive"))
      (node (ref "U$1") (pin "12") (pinfunction "OUT1_12") (pintype "bidirectional"))
    )
    (net (code "31") (name "OUT2") (class "Default")
      (node (ref "J3") (pin "P2") (pinfunction "2_P2") (pintype "passive"))
      (node (ref "U$1") (pin "11") (pinfunction "OUT2_11") (pintype "bidirectional"))
    )
    (net (code "32") (name "OUT3") (class "Default")
      (node (ref "J4") (pin "P1") (pinfunction "1_P1") (pintype "passive"))
      (node (ref "U$1") (pin "14") (pinfunction "OUT3_14") (pintype "bidirectional"))
    )
    (net (code "33") (name "OUT4") (class "Default")
      (node (ref "J4") (pin "P2") (pinfunction "2_P2") (pintype "passive"))
      (node (ref "U$1") (pin "15") (pinfunction "OUT4_15") (pintype "bidirectional"))
    )
    (net (code "34") (name "OUTN") (class "Default")
      (node (ref "IC1") (pin "8") (pinfunction "OUTN_8") (pintype "bidirectional"))
      (node (ref "J6") (pin "2") (pinfunction "2_2") (pintype "passive"))
    )
    (net (code "35") (name "OUTP") (class "Default")
      (node (ref "IC1") (pin "5") (pinfunction "OUTP_5") (pintype "bidirectional"))
      (node (ref "J6") (pin "1") (pinfunction "1_1") (pintype "passive"))
    )
    (net (code "36") (name "QSPI_CS") (class "Default")
      (node (ref "R3") (pin "1") (pinfunction "1_1") (pintype "passive"))
      (node (ref "R4") (pin "1") (pinfunction "1_1") (pintype "passive"))
      (node (ref "U1") (pin "56") (pinfunction "QSPI_CSN_56") (pintype "bidirectional"))
      (node (ref "U2") (pin "1") (pinfunction "~{CS}_1") (pintype "input"))
    )
    (net (code "37") (name "QSPI_SCLK") (class "Default")
      (node (ref "U1") (pin "52") (pinfunction "QSPI_SCLK_52") (pintype "bidirectional"))
      (node (ref "U2") (pin "6") (pinfunction "CLK_6") (pintype "input"))
    )
    (net (code "38") (name "QSPI_SD0") (class "Default")
      (node (ref "U1") (pin "53") (pinfunction "QSPI_SD0_53") (pintype "bidirectional"))
      (node (ref "U2") (pin "5") (pinfunction "DI(IO0)_5") (pintype "bidirectional"))
    )
    (net (code "39") (name "QSPI_SD1") (class "Default")
      (node (ref "U1") (pin "55") (pinfunction "QSPI_SD1_55") (pintype "bidirectional"))
      (node (ref "U2") (pin "2") (pinfunction "DO(IO1)_2") (pintype "bidirectional"))
    )
    (net (code "40") (name "QSPI_SD2") (class "Default")
      (node (ref "U1") (pin "54") (pinfunction "QSPI_SD2_54") (pintype "bidirectional"))
      (node (ref "U2") (pin "3") (pinfunction "~{WP}(IO2)_3") (pintype "bidirectional"))
    )
    (net (code "41") (name "QSPI_SD3") (class "Default")
      (node (ref "U1") (pin "51") (pinfunction "QSPI_SD3_51") (pintype "bidirectional"))
      (node (ref "U2") (pin "7") (pinfunction "~{HOLD}/~{RESET}(IO3)_7") (pintype "bidirectional"))
    )
    (net (code "42") (name "R") (class "Default")
      (node (ref "R11") (pin "1") (pinfunction "1_1") (pintype "passive"))
      (node (ref "U1") (pin "35") (pinfunction "GPIO23_35") (pintype "bidirectional"))
    )
    (net (code "43") (name "RX") (class "Default")
      (node (ref "R16") (pin "2") (pinfunction "2_2") (pintype "passive"))
      (node (ref "R17") (pin "1") (pinfunction "1_1") (pintype "passive"))
    )
    (net (code "44") (name "SCL") (class "Default")
      (node (ref "IC1") (pin "11") (pinfunction "SCL_11") (pintype "bidirectional"))
      (node (ref "J5") (pin "4") (pinfunction "SCL_4") (pintype "passive"))
      (node (ref "J7") (pin "40") (pinfunction "SCL_P_40") (pintype "bidirectional"))
      (node (ref "R9") (pin "1") (pinfunction "1_1") (pintype "passive"))
      (node (ref "U1") (pin "3") (pinfunction "GPIO1_3") (pintype "bidirectional"))
      (node (ref "U4") (pin "4") (pinfunction "SCK_4") (pintype "input"))
      (node (ref "U5") (pin "13") (pinfunction "SCX_13") (pintype "input"))
    )
    (net (code "45") (name "SDA") (class "Default")
      (node (ref "IC1") (pin "10") (pinfunction "SDA_10") (pintype "bidirectional"))
      (node (ref "J5") (pin "3") (pinfunction "SDA_3") (pintype "passive"))
      (node (ref "J7") (pin "42") (pinfunction "SDA_P_42") (pintype "bidirectional"))
      (node (ref "R8") (pin "1") (pinfunction "1_1") (pintype "passive"))
      (node (ref "U1") (pin "2") (pinfunction "GPIO0_2") (pintype "bidirectional"))
      (node (ref "U4") (pin "3") (pinfunction "SDI_3") (pintype "bidirectional"))
      (node (ref "U5") (pin "14") (pinfunction "SDX_14") (pintype "bidirectional"))
    )
    (net (code "46") (name "SWCLK") (class "Default")
      (node (ref "J1") (pin "1") (pinfunction "1_1") (pintype "passive"))
      (node (ref "U1") (pin "24") (pinfunction "SWCLK_24") (pintype "input"))
    )
    (net (code "47") (name "SWDIO") (class "Default")
      (node (ref "J1") (pin "3") (pinfunction "3_3") (pintype "passive"))
      (node (ref "U1") (pin "25") (pinfunction "SWD_25") (pintype "bidirectional"))
    )
    (net (code "48") (name "TX") (class "Default")
      (node (ref "R15") (pin "2") (pinfunction "2_2") (pintype "passive"))
      (node (ref "R18") (pin "1") (pinfunction "1_1") (pintype "passive"))
    )
    (net (code "49") (name "USB_DM_IN") (class "Default")
      (node (ref "R1") (pin "1") (pinfunction "1_1") (pintype "passive"))
      (node (ref "U1") (pin "46") (pinfunction "USB_DM_46") (pintype "bidirectional"))
    )
    (net (code "50") (name "USB_DP_IN") (class "Default")
      (node (ref "R2") (pin "1") (pinfunction "1_1") (pintype "passive"))
      (node (ref "U1") (pin "47") (pinfunction "USB_DP_47") (pintype "bidirectional"))
    )
    (net (code "51") (name "USB_N") (class "Default")
      (node (ref "J9") (pin "5") (pinfunction "D-_5") (pintype "passive"))
      (node (ref "J9") (pin "8") (pinfunction "D-_8") (pintype "passive"))
      (node (ref "R1") (pin "2") (pinfunction "2_2") (pintype "passive"))
    )
    (net (code "52") (name "USB_P") (class "Default")
      (node (ref "J9") (pin "6") (pinfunction "D+_6") (pintype "passive"))
      (node (ref "J9") (pin "7") (pinfunction "D+_7") (pintype "passive"))
      (node (ref "R2") (pin "2") (pinfunction "2_2") (pintype "passive"))
    )
    (net (code "53") (name "VIN") (class "Default")
      (node (ref "C13") (pin "1") (pinfunction "1_1") (pintype "passive"))
      (node (ref "C19") (pin "2") (pinfunction "2_2") (pintype "passive"))
      (node (ref "D1") (pin "C") (pinfunction "C_C") (pintype "passive"))
      (node (ref "Q1") (pin "2") (pinfunction "S_2") (pintype "bidirectional"))
      (node (ref "U$1") (pin "1") (pinfunction "VM_1") (pintype "bidirectional"))
      (node (ref "U3") (pin "1") (pinfunction "~{SD}_1") (pintype "passive"))
      (node (ref "U3") (pin "2") (pinfunction "VIN_2") (pintype "power_in"))
    )
    (net (code "54") (name "VOUT") (class "Default")
      (node (ref "C1") (pin "1") (pinfunction "1_1") (pintype "passive"))
      (node (ref "C2") (pin "1") (pinfunction "1_1") (pintype "passive"))
      (node (ref "C3") (pin "1") (pinfunction "1_1") (pintype "passive"))
      (node (ref "U1") (pin "23") (pinfunction "DVDD_23") (pintype "power_in"))
      (node (ref "U1") (pin "45") (pinfunction "VREG_VOUT_45") (pintype "output"))
      (node (ref "U1") (pin "50") (pinfunction "DVDD_50") (pintype "power_in"))
    )
    (net (code "55") (name "V_USB") (class "Default")
      (node (ref "D1") (pin "A") (pinfunction "A_A") (pintype "passive"))
      (node (ref "J9") (pin "11") (pinfunction "VBUS_11") (pintype "power_in"))
      (node (ref "J9") (pin "2") (pinfunction "VBUS_2") (pintype "power_in"))
      (node (ref "Q1") (pin "1") (pinfunction "G_1") (pintype "bidirectional"))
      (node (ref "R7") (pin "2") (pinfunction "2_2") (pintype "passive"))
    )
    (net (code "56") (name "XIN") (class "Default")
      (node (ref "C20") (pin "1") (pinfunction "1_1") (pintype "passive"))
      (node (ref "U1") (pin "20") (pinfunction "XIN_20") (pintype "input"))
      (node (ref "Y1") (pin "2") (pinfunction "2_2") (pintype "passive"))
    )
    (net (code "57") (name "XOUT") (class "Default")
      (node (ref "R14") (pin "1") (pinfunction "1_1") (pintype "passive"))
      (node (ref "U1") (pin "21") (pinfunction "XOUT_21") (pintype "output"))
    )
    (net (code "58") (name "XOUT_R") (class "Default")
      (node (ref "C21") (pin "1") (pinfunction "1_1") (pintype "passive"))
      (node (ref "R14") (pin "2") (pinfunction "2_2") (pintype "passive"))
      (node (ref "Y1") (pin "1") (pinfunction "1_1") (pintype "passive"))
    )
    (net (code "59") (name "unconnected-(IC1-GPI_0{slash}_PWM-Pad3)") (class "Default")
      (node (ref "IC1") (pin "3") (pinfunction "GPI_0/_PWM_3") (pintype "bidirectional"))
    )
    (net (code "60") (name "unconnected-(IC1-GPI_1-Pad2)") (class "Default")
      (node (ref "IC1") (pin "2") (pinfunction "GPI_1_2") (pintype "bidirectional"))
    )
    (net (code "61") (name "unconnected-(IC1-GPI_2-Pad1)") (class "Default")
      (node (ref "IC1") (pin "1") (pinfunction "GPI_2_1") (pintype "bidirectional"))
    )
    (net (code "62") (name "unconnected-(IC1-NIRQ-Pad12)") (class "Default")
      (node (ref "IC1") (pin "12") (pinfunction "NIRQ_12") (pintype "bidirectional"))
    )
    (net (code "63") (name "unconnected-(J7-AUX1-Pad46)") (class "Default")
      (node (ref "J7") (pin "46") (pinfunction "AUX1_46") (pintype "bidirectional"))
    )
    (net (code "64") (name "unconnected-(J7-AUX2-Pad48)") (class "Default")
      (node (ref "J7") (pin "48") (pinfunction "AUX2_48") (pintype "bidirectional"))
    )
    (net (code "65") (name "unconnected-(J7-AUX3-Pad50)") (class "Default")
      (node (ref "J7") (pin "50") (pinfunction "AUX3_50") (pintype "bidirectional"))
    )
    (net (code "66") (name "unconnected-(J7-AUX4-Pad52)") (class "Default")
      (node (ref "J7") (pin "52") (pinfunction "AUX4_52") (pintype "bidirectional"))
    )
    (net (code "67") (name "unconnected-(J7-AUX5-Pad38)") (class "Default")
      (node (ref "J7") (pin "38") (pinfunction "AUX5_38") (pintype "bidirectional"))
    )
    (net (code "68") (name "unconnected-(J7-AUX_EN_P-Pad56)") (class "Default")
      (node (ref "J7") (pin "56") (pinfunction "AUX_EN_P_56") (pintype "bidirectional"))
    )
    (net (code "69") (name "unconnected-(J7-AUX_RX_P-Pad58)") (class "Default")
      (node (ref "J7") (pin "58") (pinfunction "AUX_RX_P_58") (pintype "bidirectional"))
    )
    (net (code "70") (name "unconnected-(J7-AUX_TX_P-Pad60)") (class "Default")
      (node (ref "J7") (pin "60") (pinfunction "AUX_TX_P_60") (pintype "bidirectional"))
    )
    (net (code "71") (name "unconnected-(J7-NC-Pad1)") (class "Default")
      (node (ref "J7") (pin "1") (pinfunction "NC_1") (pintype "bidirectional"))
    )
    (net (code "72") (name "unconnected-(J7-NC-Pad15)") (class "Default")
      (node (ref "J7") (pin "15") (pinfunction "NC_15") (pintype "bidirectional"))
    )
    (net (code "73") (name "unconnected-(J7-NC-Pad17)") (class "Default")
      (node (ref "J7") (pin "17") (pinfunction "NC_17") (pintype "bidirectional"))
    )
    (net (code "74") (name "unconnected-(J7-NC-Pad19)") (class "Default")
      (node (ref "J7") (pin "19") (pinfunction "NC_19") (pintype "bidirectional"))
    )
    (net (code "75") (name "unconnected-(J7-NC-Pad21)") (class "Default")
      (node (ref "J7") (pin "21") (pinfunction "NC_21") (pintype "bidirectional"))
    )
    (net (code "76") (name "unconnected-(J7-NC-Pad23)") (class "Default")
      (node (ref "J7") (pin "23") (pinfunction "NC_23") (pintype "bidirectional"))
    )
    (net (code "77") (name "unconnected-(J7-NC-Pad32)") (class "Default")
      (node (ref "J7") (pin "32") (pinfunction "NC_32") (pintype "bidirectional"))
    )
    (net (code "78") (name "unconnected-(J7-NC-Pad34)") (class "Default")
      (node (ref "J7") (pin "34") (pinfunction "NC_34") (pintype "bidirectional"))
    )
    (net (code "79") (name "unconnected-(J7-NC-Pad35)") (class "Default")
      (node (ref "J7") (pin "35") (pinfunction "NC_35") (pintype "bidirectional"))
    )
    (net (code "80") (name "unconnected-(J7-NC-Pad36)") (class "Default")
      (node (ref "J7") (pin "36") (pinfunction "NC_36") (pintype "bidirectional"))
    )
    (net (code "81") (name "unconnected-(J7-NC-Pad37)") (class "Default")
      (node (ref "J7") (pin "37") (pinfunction "NC_37") (pintype "bidirectional"))
    )
    (net (code "82") (name "unconnected-(J7-NC-Pad41)") (class "Default")
      (node (ref "J7") (pin "41") (pinfunction "NC_41") (pintype "bidirectional"))
    )
    (net (code "83") (name "unconnected-(J7-NC-Pad43)") (class "Default")
      (node (ref "J7") (pin "43") (pinfunction "NC_43") (pintype "bidirectional"))
    )
    (net (code "84") (name "unconnected-(J7-NC-Pad44)") (class "Default")
      (node (ref "J7") (pin "44") (pinfunction "NC_44") (pintype "bidirectional"))
    )
    (net (code "85") (name "unconnected-(J7-NC-Pad47)") (class "Default")
      (node (ref "J7") (pin "47") (pinfunction "NC_47") (pintype "bidirectional"))
    )
    (net (code "86") (name "unconnected-(J7-NC-Pad49)") (class "Default")
      (node (ref "J7") (pin "49") (pinfunction "NC_49") (pintype "bidirectional"))
    )
    (net (code "87") (name "unconnected-(J7-NC-Pad53)") (class "Default")
      (node (ref "J7") (pin "53") (pinfunction "NC_53") (pintype "bidirectional"))
    )
    (net (code "88") (name "unconnected-(J7-NC-Pad55)") (class "Default")
      (node (ref "J7") (pin "55") (pinfunction "NC_55") (pintype "bidirectional"))
    )
    (net (code "89") (name "unconnected-(J7-NC-Pad59)") (class "Default")
      (node (ref "J7") (pin "59") (pinfunction "NC_59") (pintype "bidirectional"))
    )
    (net (code "90") (name "unconnected-(J7-NC-Pad61)") (class "Default")
      (node (ref "J7") (pin "61") (pinfunction "NC_61") (pintype "bidirectional"))
    )
    (net (code "91") (name "unconnected-(J7-NC-Pad63)") (class "Default")
      (node (ref "J7") (pin "63") (pinfunction "NC_63") (pintype "bidirectional"))
    )
    (net (code "92") (name "unconnected-(J7-NC-Pad65)") (class "Default")
      (node (ref "J7") (pin "65") (pinfunction "NC_65") (pintype "bidirectional"))
    )
    (net (code "93") (name "unconnected-(J7-NC-Pad66)") (class "Default")
      (node (ref "J7") (pin "66") (pinfunction "NC_66") (pintype "bidirectional"))
    )
    (net (code "94") (name "unconnected-(J7-NC-Pad68)") (class "Default")
      (node (ref "J7") (pin "68") (pinfunction "NC_68") (pintype "bidirectional"))
    )
    (net (code "95") (name "unconnected-(J7-NC-Pad69)") (class "Default")
      (node (ref "J7") (pin "69") (pinfunction "NC_69") (pintype "bidirectional"))
    )
    (net (code "96") (name "unconnected-(J7-NC-Pad75)") (class "Default")
      (node (ref "J7") (pin "75") (pinfunction "NC_75") (pintype "bidirectional"))
    )
    (net (code "97") (name "unconnected-(J7-SIM_CLK-Pad14)") (class "Default")
      (node (ref "J7") (pin "14") (pinfunction "SIM_CLK_14") (pintype "bidirectional"))
    )
    (net (code "98") (name "unconnected-(J7-SIM_IO-Pad12)") (class "Default")
      (node (ref "J7") (pin "12") (pinfunction "SIM_IO_12") (pintype "bidirectional"))
    )
    (net (code "99") (name "unconnected-(J7-SIM_PRES-Pad16)") (class "Default")
      (node (ref "J7") (pin "16") (pinfunction "SIM_PRES_16") (pintype "bidirectional"))
    )
    (net (code "100") (name "unconnected-(J7-SIM_RST-Pad10)") (class "Default")
      (node (ref "J7") (pin "10") (pinfunction "SIM_RST_10") (pintype "bidirectional"))
    )
    (net (code "101") (name "unconnected-(J7-SIM_VCC-Pad8)") (class "Default")
      (node (ref "J7") (pin "8") (pinfunction "SIM_VCC_8") (pintype "bidirectional"))
    )
    (net (code "102") (name "unconnected-(J7-UDB_DM-Pad9)") (class "Default")
      (node (ref "J7") (pin "9") (pinfunction "UDB_DM_9") (pintype "bidirectional"))
    )
    (net (code "103") (name "unconnected-(J7-USB_DP-Pad7)") (class "Default")
      (node (ref "J7") (pin "7") (pinfunction "USB_DP_7") (pintype "bidirectional"))
    )
    (net (code "104") (name "unconnected-(J7-VUSB-Pad13)") (class "Default")
      (node (ref "J7") (pin "13") (pinfunction "VUSB_13") (pintype "bidirectional"))
    )
    (net (code "105") (name "unconnected-(J9-SBU1-Pad10)") (class "Default")
      (node (ref "J9") (pin "10") (pinfunction "SBU1_10") (pintype "passive"))
    )
    (net (code "106") (name "unconnected-(J9-SBU2-Pad4)") (class "Default")
      (node (ref "J9") (pin "4") (pinfunction "SBU2_4") (pintype "passive"))
    )
    (net (code "107") (name "unconnected-(U$1-NC-Pad2)") (class "Default")
      (node (ref "U$1") (pin "2") (pinfunction "NC_2") (pintype "bidirectional"))
    )
    (net (code "108") (name "unconnected-(U$1-NC2-Pad5)") (class "Default")
      (node (ref "U$1") (pin "5") (pinfunction "NC2_5") (pintype "bidirectional"))
    )
    (net (code "109") (name "unconnected-(U$1-NC3-Pad8)") (class "Default")
      (node (ref "U$1") (pin "8") (pinfunction "NC3_8") (pintype "bidirectional"))
    )
    (net (code "110") (name "unconnected-(U$1-NC4-Pad16)") (class "Default")
      (node (ref "U$1") (pin "16") (pinfunction "NC4_16") (pintype "bidirectional"))
    )
    (net (code "111") (name "unconnected-(U$1-NC5-Pad13)") (class "Default")
      (node (ref "U$1") (pin "13") (pinfunction "NC5_13") (pintype "bidirectional"))
    )
    (net (code "112") (name "unconnected-(U$1-NC6-Pad10)") (class "Default")
      (node (ref "U$1") (pin "10") (pinfunction "NC6_10") (pintype "bidirectional"))
    )
    (net (code "113") (name "unconnected-(U1-GPIO8-Pad11)") (class "Default")
      (node (ref "U1") (pin "11") (pinfunction "GPIO8_11") (pintype "bidirectional"))
    )
    (net (code "114") (name "unconnected-(U1-GPIO9-Pad12)") (class "Default")
      (node (ref "U1") (pin "12") (pinfunction "GPIO9_12") (pintype "bidirectional"))
    )
    (net (code "115") (name "unconnected-(U1-GPIO10-Pad13)") (class "Default")
      (node (ref "U1") (pin "13") (pinfunction "GPIO10_13") (pintype "bidirectional"))
    )
    (net (code "116") (name "unconnected-(U1-GPIO11-Pad14)") (class "Default")
      (node (ref "U1") (pin "14") (pinfunction "GPIO11_14") (pintype "bidirectional"))
    )
    (net (code "117") (name "unconnected-(U1-GPIO12-Pad15)") (class "Default")
      (node (ref "U1") (pin "15") (pinfunction "GPIO12_15") (pintype "bidirectional"))
    )
    (net (code "118") (name "unconnected-(U1-GPIO13-Pad16)") (class "Default")
      (node (ref "U1") (pin "16") (pinfunction "GPIO13_16") (pintype "bidirectional"))
    )
    (net (code "119") (name "unconnected-(U1-GPIO14-Pad17)") (class "Default")
      (node (ref "U1") (pin "17") (pinfunction "GPIO14_17") (pintype "bidirectional"))
    )
    (net (code "120") (name "unconnected-(U1-GPIO15-Pad18)") (class "Default")
      (node (ref "U1") (pin "18") (pinfunction "GPIO15_18") (pintype "bidirectional"))
    )
    (net (code "121") (name "unconnected-(U1-GPIO26{slash}ADC0-Pad38)") (class "Default")
      (node (ref "U1") (pin "38") (pinfunction "GPIO26/ADC0_38") (pintype "bidirectional"))
    )
    (net (code "122") (name "unconnected-(U1-GPIO27{slash}ADC1-Pad39)") (class "Default")
      (node (ref "U1") (pin "39") (pinfunction "GPIO27/ADC1_39") (pintype "bidirectional"))
    )
    (net (code "123") (name "unconnected-(U1-GPIO28{slash}ADC2-Pad40)") (class "Default")
      (node (ref "U1") (pin "40") (pinfunction "GPIO28/ADC2_40") (pintype "bidirectional"))
    )
    (net (code "124") (name "unconnected-(U1-GPIO29{slash}ADC3-Pad41)") (class "Default")
      (node (ref "U1") (pin "41") (pinfunction "GPIO29/ADC3_41") (pintype "bidirectional"))
    )
    (net (code "125") (name "unconnected-(U5-ASCX-Pad3)") (class "Default")
      (node (ref "U5") (pin "3") (pinfunction "ASCX_3") (pintype "bidirectional"))
    )
    (net (code "126") (name "unconnected-(U5-ASDX-Pad2)") (class "Default")
      (node (ref "U5") (pin "2") (pinfunction "ASDX_2") (pintype "bidirectional"))
    )
    (net (code "127") (name "unconnected-(U5-OSCB-Pad10)") (class "Default")
      (node (ref "U5") (pin "10") (pinfunction "OSCB_10") (pintype "input"))
    )
    (net (code "128") (name "unconnected-(U5-OSDO-Pad11)") (class "Default")
      (node (ref "U5") (pin "11") (pinfunction "OSDO_11") (pintype "output"))
    )
    (net (code "129") (name "~{BOOT}") (class "Default")
      (node (ref "R4") (pin "2") (pinfunction "2_2") (pintype "passive"))
      (node (ref "S1") (pin "1") (pinfunction "1_1") (pintype "passive"))
    )
    (net (code "130") (name "~{RESET}") (class "Default")
      (node (ref "S2") (pin "1") (pinfunction "1_1") (pintype "passive"))
      (node (ref "U1") (pin "26") (pinfunction "RUN_26") (pintype "input"))
    )
  )
)
